# Sch_Sheet_Template.net
KiCad netlist of a schematic drawn in Altium Designer
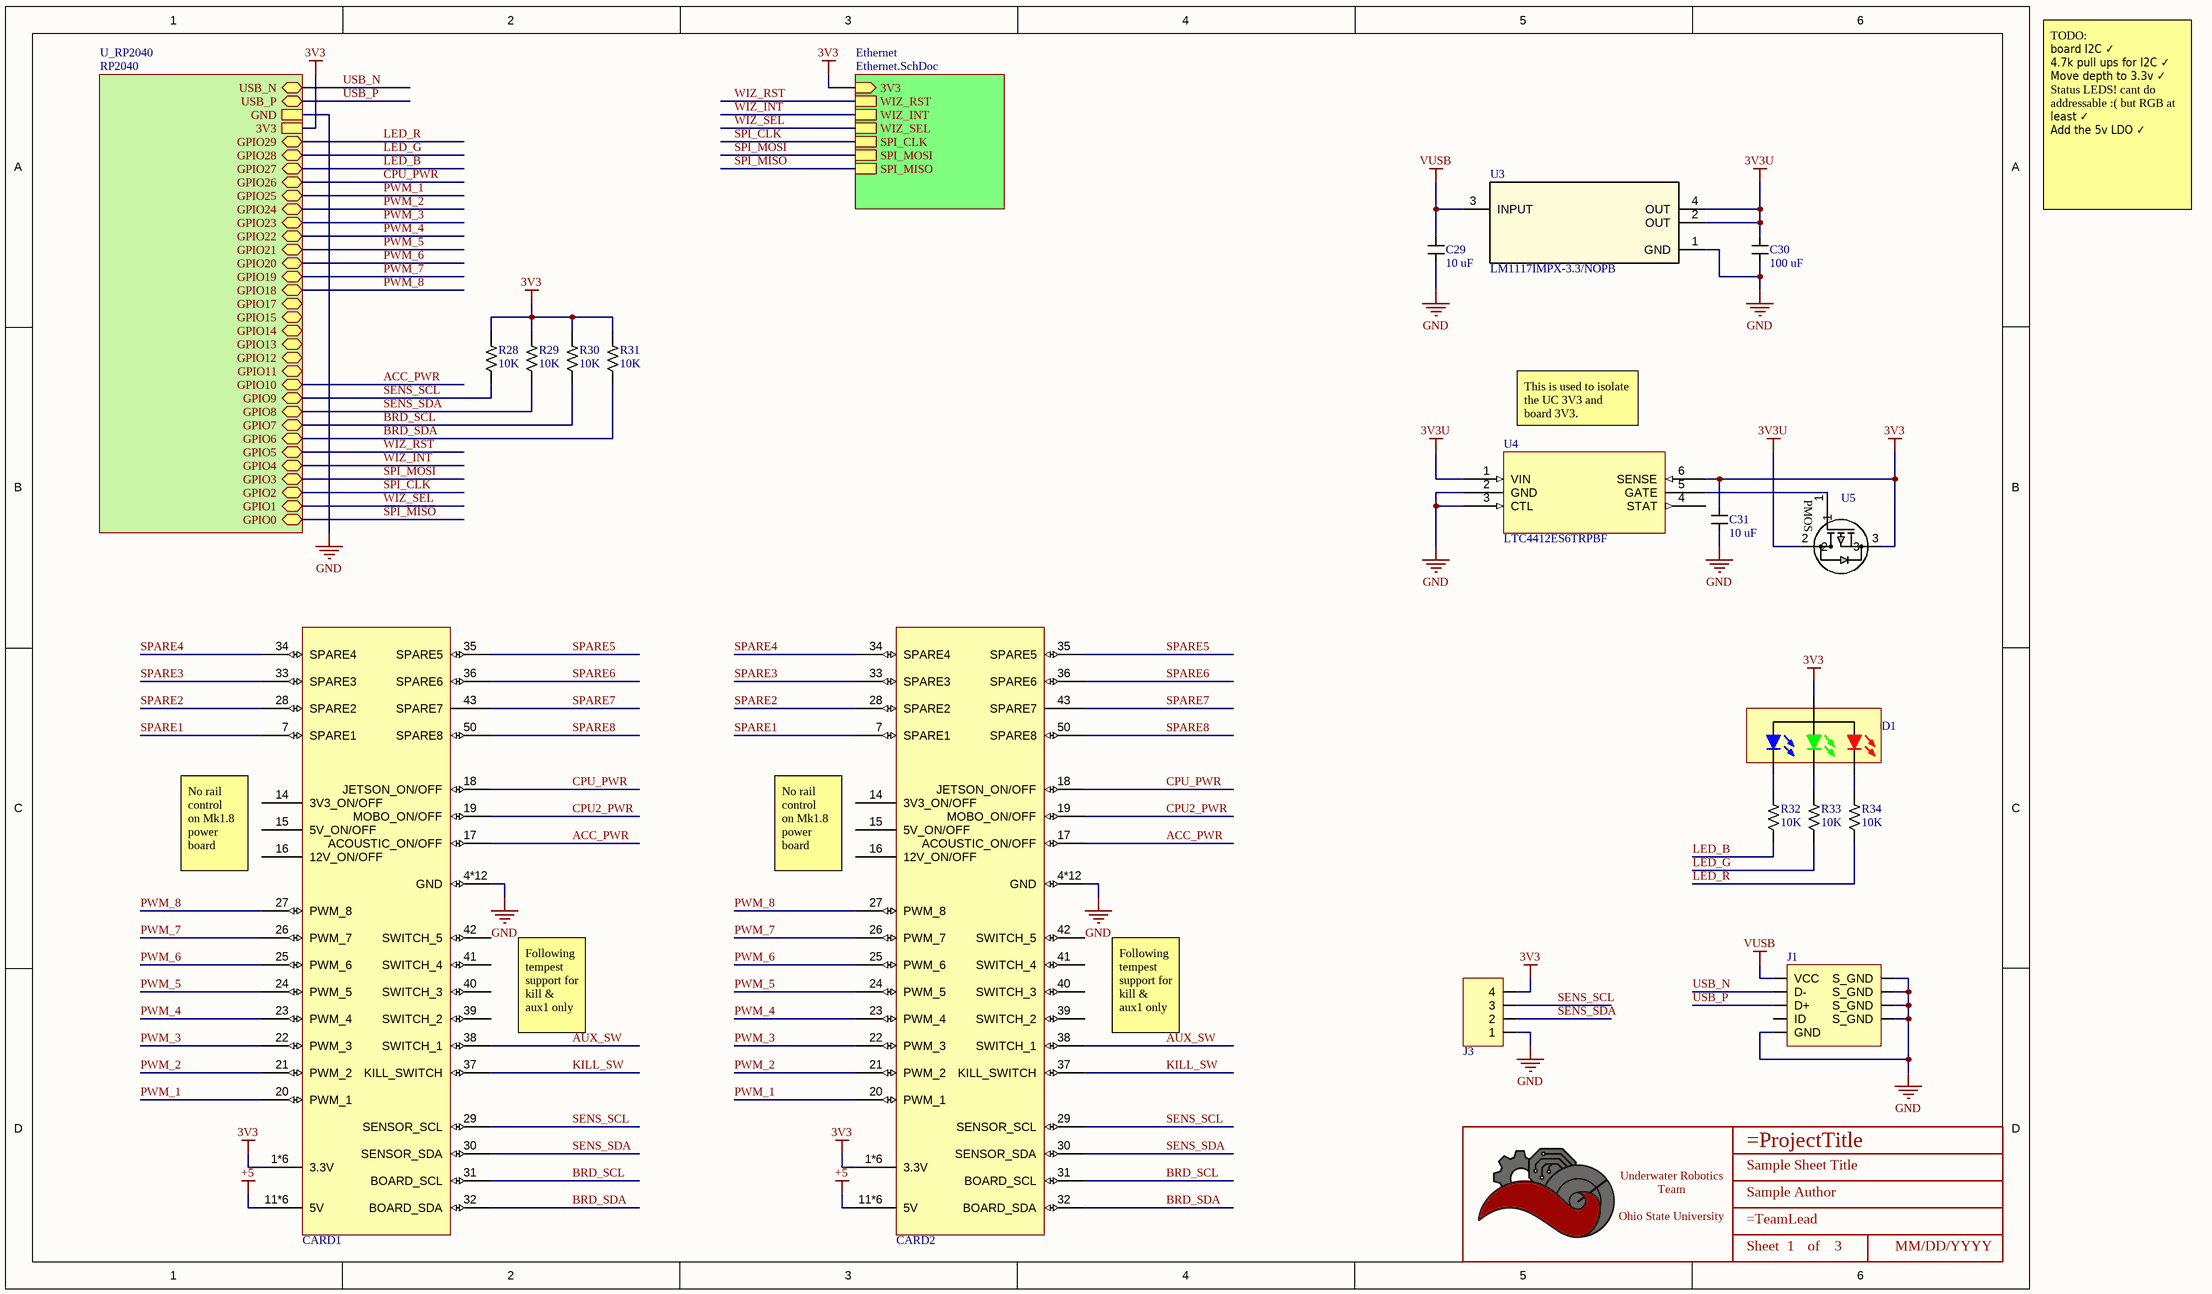
[diagram p0: Sch_Sheet_Template.SchDoc]

(export (version "E")
  (design (tool "Eeschema 10.0.6"))
  (components
    (comp (ref "*")
      (value "Title_Block")
      (footprint "LOGO")
      (description "UWRT Schematic Title Block Template\r\n\r\nCreated June 2021, Dylan Trainor")
      (libsource (lib "UWRT") (part "Title_Block"))
    )
    (comp (ref "C29")
      (value "10uF Ceramic 6.3V")
      (footprint "CAPACITOR_0603")
      (description "Cap 10uF 6.3V +/-20%\r\nCeramic 0603")
      (fields
        (field (name "TOLERANCE") "+/- 20%")
        (field (name "VOLTAGE") "6.3V")
        (field (name "VALUE (UF)") "10 uF")
        (field (name "MADE BY") "Flip B")
      )
      (libsource (lib "Capacitors") (part "CAPACITOR_10uF_0603"))
    )
    (comp (ref "C30")
      (value "100uF Ceramic 6.3V")
      (footprint "CAPACITOR_0603")
      (description "Cap 100uF 6.3V +/-20%\r\nCeramic 0603")
      (fields
        (field (name "TOLERANCE") "+/- 20%")
        (field (name "VOLTAGE") "6.3V")
        (field (name "VALUE (UF)") "100 uF")
        (field (name "MADE BY") "Dylan Trainor")
      )
      (libsource (lib "Capacitors") (part "CAPACITOR_100uF_0603"))
    )
    (comp (ref "C31")
      (value "10uF Ceramic 6.3V")
      (footprint "CAPACITOR_0603")
      (description "Cap 10uF 6.3V +/-20%\r\nCeramic 0603")
      (fields
        (field (name "TOLERANCE") "+/- 20%")
        (field (name "VOLTAGE") "6.3V")
        (field (name "VALUE (UF)") "10 uF")
        (field (name "MADE BY") "Flip B")
      )
      (libsource (lib "Capacitors") (part "CAPACITOR_10uF_0603"))
    )
    (comp (ref "CARD1")
      (value "BACKPLANE_EDGE_SOCKET")
      (footprint "SOCKET_BACKPLANE_EDGE_CONN")
      (description "Backplane Edge Socket")
      (fields (field (name "MADE BY") "Robert Pafford"))
      (libsource (lib "Connectors") (part "BACKPLANE_EDGE_SOCKET"))
    )
    (comp (ref "CARD2")
      (value "BACKPLANE_EDGE_SOCKET")
      (footprint "SOCKET_BACKPLANE_EDGE_CONN")
      (description "Backplane Edge Socket")
      (fields (field (name "MADE BY") "Robert Pafford"))
      (libsource (lib "Connectors") (part "BACKPLANE_EDGE_SOCKET"))
    )
    (comp (ref "D1")
      (value "EAST1616RGBB4")
      (footprint "LED_0606_4SMD")
      (description "LED RGB CLEAR 4SMD")
      (fields (field (name "MADE BY") "Robert Pafford"))
      (libsource (lib "Diodes") (part "LED_RGB_4SMD"))
    )
    (comp (ref "J1")
      (value "USB_MICRO R/A")
      (footprint "CONN_MINIUSB")
      (description "Amphenol Micro USB-B\r\nUSB2.0 5 Pin Right Angle SMD")
      (fields (field (name "MANUFACTURER") "Amphenol") (field (name "CREATED BY") "Flip B"))
      (libsource (lib "Connectors") (part "CONN_MICROUSB"))
    )
    (comp (ref "J3")
      (value "4 POS R/A")
      (footprint "CONN_MOLEX_MINIFIT JR_4 POS_R/A")
      (description "Molex Minifit Jr. 5569 \r\n4 Pos R/A Natural")
      (fields (field (name "MANUFACTURER") "Molex") (field (name "CREATED BY") "Flip B"))
      (libsource (lib "Connectors") (part "CONN_MOLEX_MINIFIT JR_4POS_R/A"))
    )
    (comp (ref "R28")
      (value "10k Ohm 5% 1/10W")
      (footprint "RESISTOR_0603")
      (description "RES 10k OHM 5% 1/10W 0603")
      (fields
        (field (name "TOLERANCE") "+/- 5%")
        (field (name "VALUE  (OHMS)") "10K")
        (field (name "MADE BY") "Robert Pafford")
      )
      (libsource (lib "Resistors") (part "RESISTOR_10K_0603"))
    )
    (comp (ref "R29")
      (value "10k Ohm 5% 1/10W")
      (footprint "RESISTOR_0603")
      (description "RES 10k OHM 5% 1/10W 0603")
      (fields
        (field (name "TOLERANCE") "+/- 5%")
        (field (name "VALUE  (OHMS)") "10K")
        (field (name "MADE BY") "Robert Pafford")
      )
      (libsource (lib "Resistors") (part "RESISTOR_10K_0603"))
    )
    (comp (ref "R30")
      (value "10k Ohm 5% 1/10W")
      (footprint "RESISTOR_0603")
      (description "RES 10k OHM 5% 1/10W 0603")
      (fields
        (field (name "TOLERANCE") "+/- 5%")
        (field (name "VALUE  (OHMS)") "10K")
        (field (name "MADE BY") "Robert Pafford")
      )
      (libsource (lib "Resistors") (part "RESISTOR_10K_0603"))
    )
    (comp (ref "R31")
      (value "10k Ohm 5% 1/10W")
      (footprint "RESISTOR_0603")
      (description "RES 10k OHM 5% 1/10W 0603")
      (fields
        (field (name "TOLERANCE") "+/- 5%")
        (field (name "VALUE  (OHMS)") "10K")
        (field (name "MADE BY") "Robert Pafford")
      )
      (libsource (lib "Resistors") (part "RESISTOR_10K_0603"))
    )
    (comp (ref "R32")
      (value "10k Ohm 5% 1/10W")
      (footprint "RESISTOR_0603")
      (description "RES 10k OHM 5% 1/10W 0603")
      (fields
        (field (name "TOLERANCE") "+/- 5%")
        (field (name "VALUE  (OHMS)") "10K")
        (field (name "MADE BY") "Robert Pafford")
      )
      (libsource (lib "Resistors") (part "RESISTOR_10K_0603"))
    )
    (comp (ref "R33")
      (value "10k Ohm 5% 1/10W")
      (footprint "RESISTOR_0603")
      (description "RES 10k OHM 5% 1/10W 0603")
      (fields
        (field (name "TOLERANCE") "+/- 5%")
        (field (name "VALUE  (OHMS)") "10K")
        (field (name "MADE BY") "Robert Pafford")
      )
      (libsource (lib "Resistors") (part "RESISTOR_10K_0603"))
    )
    (comp (ref "R34")
      (value "10k Ohm 5% 1/10W")
      (footprint "RESISTOR_0603")
      (description "RES 10k OHM 5% 1/10W 0603")
      (fields
        (field (name "TOLERANCE") "+/- 5%")
        (field (name "VALUE  (OHMS)") "10K")
        (field (name "MADE BY") "Robert Pafford")
      )
      (libsource (lib "Resistors") (part "RESISTOR_10K_0603"))
    )
    (comp (ref "U3")
      (value "LM1117IMPX-3.3/NOPB")
      (footprint "SOT-223-4")
      (description "IC REG LIN 3.3V 800MA SOT223-4")
      (fields
        (field (name "PARTNUMBER") "LM1117IMP-3.3/NOPB")
        (field (name "MANUFACTURER") "Texas Instruments")
        (field (name "CREATED BY") "Dylan T")
      )
      (libsource (lib "Converter") (part "LM1117IMPX-3.3/NOPB"))
    )
    (comp (ref "U4")
      (value "LTC4412ES6TRPBF")
      (footprint "Integrated Circuits:TSOT-23_S6")
      (description "OR Controller Source Selector Switch P-Channel 2:1 TSOT-23-6")
      (fields (field (name "MP") "LTC4412ES6#TRPBF") (field (name "MF") "Analog Devices"))
      (libsource (lib "Integrated Circuits") (part "LTC4412ES6TRPBF"))
    )
    (comp (ref "U5")
      (value "MOSFET P-CHANNEL 20V 4.7A SOT23")
      (footprint "SOT-23-3")
      (description "P-Channel 20 V 4.7A (Tc) 1.56W (Tc) Surface Mount SOT-23")
      (fields
        (field (name "MANUFACTURER_PART_NUMBER") "TSM500P02CX")
        (field (name "CREATED BY") "Robert Pafford")
      )
      (libsource (lib "Transistors") (part "TSM500P02CX"))
    )
  )
  (nets
    (net (code "1") (name "+5") (class "Default")
      (node (ref "CARD1") (pin "11*6") (pinfunction "5V_11*6") (pintype "power_in"))
      (node (ref "CARD2") (pin "11*6") (pinfunction "5V_11*6") (pintype "power_in"))
    )
    (net (code "2") (name "/ACC_PWR") (class "Default")
      (node (ref "CARD1") (pin "17") (pinfunction "ACOUSTIC_ON/OFF_17") (pintype "bidirectional"))
      (node (ref "CARD2") (pin "17") (pinfunction "ACOUSTIC_ON/OFF_17") (pintype "bidirectional"))
    )
    (net (code "3") (name "/AUX_SW") (class "Default")
      (node (ref "CARD1") (pin "38") (pinfunction "SWITCH_1_38") (pintype "bidirectional"))
      (node (ref "CARD2") (pin "38") (pinfunction "SWITCH_1_38") (pintype "bidirectional"))
    )
    (net (code "4") (name "/BRD_SCL") (class "Default")
      (node (ref "CARD1") (pin "31") (pinfunction "BOARD_SCL_31") (pintype "bidirectional"))
      (node (ref "CARD2") (pin "31") (pinfunction "BOARD_SCL_31") (pintype "bidirectional"))
      (node (ref "R30") (pin "2") (pinfunction "2_2") (pintype "passive"))
    )
    (net (code "5") (name "/BRD_SDA") (class "Default")
      (node (ref "CARD1") (pin "32") (pinfunction "BOARD_SDA_32") (pintype "bidirectional"))
      (node (ref "CARD2") (pin "32") (pinfunction "BOARD_SDA_32") (pintype "bidirectional"))
      (node (ref "R31") (pin "2") (pinfunction "2_2") (pintype "passive"))
    )
    (net (code "6") (name "/CPU2_PWR") (class "Default")
      (node (ref "CARD1") (pin "19") (pinfunction "MOBO_ON/OFF_19") (pintype "bidirectional"))
      (node (ref "CARD2") (pin "19") (pinfunction "MOBO_ON/OFF_19") (pintype "bidirectional"))
    )
    (net (code "7") (name "/CPU_PWR") (class "Default")
      (node (ref "CARD1") (pin "18") (pinfunction "JETSON_ON/OFF_18") (pintype "bidirectional"))
      (node (ref "CARD2") (pin "18") (pinfunction "JETSON_ON/OFF_18") (pintype "bidirectional"))
    )
    (net (code "14") (name "/KILL_SW") (class "Default")
      (node (ref "CARD1") (pin "37") (pinfunction "KILL_SWITCH_37") (pintype "bidirectional"))
      (node (ref "CARD2") (pin "37") (pinfunction "KILL_SWITCH_37") (pintype "bidirectional"))
    )
    (net (code "15") (name "/LED_B") (class "Default")
      (node (ref "R32") (pin "2") (pinfunction "2_2") (pintype "passive"))
    )
    (net (code "16") (name "/LED_G") (class "Default")
      (node (ref "R33") (pin "2") (pinfunction "2_2") (pintype "passive"))
    )
    (net (code "17") (name "/LED_R") (class "Default")
      (node (ref "R34") (pin "2") (pinfunction "2_2") (pintype "passive"))
    )
    (net (code "18") (name "/PWM_1") (class "Default")
      (node (ref "CARD1") (pin "20") (pinfunction "PWM_1_20") (pintype "bidirectional"))
      (node (ref "CARD2") (pin "20") (pinfunction "PWM_1_20") (pintype "bidirectional"))
    )
    (net (code "19") (name "/PWM_2") (class "Default")
      (node (ref "CARD1") (pin "21") (pinfunction "PWM_2_21") (pintype "bidirectional"))
      (node (ref "CARD2") (pin "21") (pinfunction "PWM_2_21") (pintype "bidirectional"))
    )
    (net (code "20") (name "/PWM_3") (class "Default")
      (node (ref "CARD1") (pin "22") (pinfunction "PWM_3_22") (pintype "bidirectional"))
      (node (ref "CARD2") (pin "22") (pinfunction "PWM_3_22") (pintype "bidirectional"))
    )
    (net (code "21") (name "/PWM_4") (class "Default")
      (node (ref "CARD1") (pin "23") (pinfunction "PWM_4_23") (pintype "bidirectional"))
      (node (ref "CARD2") (pin "23") (pinfunction "PWM_4_23") (pintype "bidirectional"))
    )
    (net (code "22") (name "/PWM_5") (class "Default")
      (node (ref "CARD1") (pin "24") (pinfunction "PWM_5_24") (pintype "bidirectional"))
      (node (ref "CARD2") (pin "24") (pinfunction "PWM_5_24") (pintype "bidirectional"))
    )
    (net (code "23") (name "/PWM_6") (class "Default")
      (node (ref "CARD1") (pin "25") (pinfunction "PWM_6_25") (pintype "bidirectional"))
      (node (ref "CARD2") (pin "25") (pinfunction "PWM_6_25") (pintype "bidirectional"))
    )
    (net (code "24") (name "/PWM_7") (class "Default")
      (node (ref "CARD1") (pin "26") (pinfunction "PWM_7_26") (pintype "bidirectional"))
      (node (ref "CARD2") (pin "26") (pinfunction "PWM_7_26") (pintype "bidirectional"))
    )
    (net (code "25") (name "/PWM_8") (class "Default")
      (node (ref "CARD1") (pin "27") (pinfunction "PWM_8_27") (pintype "bidirectional"))
      (node (ref "CARD2") (pin "27") (pinfunction "PWM_8_27") (pintype "bidirectional"))
    )
    (net (code "26") (name "/SENS_SCL") (class "Default")
      (node (ref "CARD1") (pin "29") (pinfunction "SENSOR_SCL_29") (pintype "bidirectional"))
      (node (ref "CARD2") (pin "29") (pinfunction "SENSOR_SCL_29") (pintype "bidirectional"))
      (node (ref "J3") (pin "3") (pinfunction "3_3") (pintype "passive"))
      (node (ref "R28") (pin "2") (pinfunction "2_2") (pintype "passive"))
    )
    (net (code "27") (name "/SENS_SDA") (class "Default")
      (node (ref "CARD1") (pin "30") (pinfunction "SENSOR_SDA_30") (pintype "bidirectional"))
      (node (ref "CARD2") (pin "30") (pinfunction "SENSOR_SDA_30") (pintype "bidirectional"))
      (node (ref "J3") (pin "2") (pinfunction "2_2") (pintype "passive"))
      (node (ref "R29") (pin "2") (pinfunction "2_2") (pintype "passive"))
    )
    (net (code "28") (name "/SPARE1") (class "Default")
      (node (ref "CARD1") (pin "7") (pinfunction "SPARE1_7") (pintype "bidirectional"))
      (node (ref "CARD2") (pin "7") (pinfunction "SPARE1_7") (pintype "bidirectional"))
    )
    (net (code "29") (name "/SPARE2") (class "Default")
      (node (ref "CARD1") (pin "28") (pinfunction "SPARE2_28") (pintype "bidirectional"))
      (node (ref "CARD2") (pin "28") (pinfunction "SPARE2_28") (pintype "bidirectional"))
    )
    (net (code "30") (name "/SPARE3") (class "Default")
      (node (ref "CARD1") (pin "33") (pinfunction "SPARE3_33") (pintype "bidirectional"))
      (node (ref "CARD2") (pin "33") (pinfunction "SPARE3_33") (pintype "bidirectional"))
    )
    (net (code "31") (name "/SPARE4") (class "Default")
      (node (ref "CARD1") (pin "34") (pinfunction "SPARE4_34") (pintype "bidirectional"))
      (node (ref "CARD2") (pin "34") (pinfunction "SPARE4_34") (pintype "bidirectional"))
    )
    (net (code "32") (name "/SPARE5") (class "Default")
      (node (ref "CARD1") (pin "35") (pinfunction "SPARE5_35") (pintype "bidirectional"))
      (node (ref "CARD2") (pin "35") (pinfunction "SPARE5_35") (pintype "bidirectional"))
    )
    (net (code "33") (name "/SPARE6") (class "Default")
      (node (ref "CARD1") (pin "36") (pinfunction "SPARE6_36") (pintype "bidirectional"))
      (node (ref "CARD2") (pin "36") (pinfunction "SPARE6_36") (pintype "bidirectional"))
    )
    (net (code "34") (name "/SPARE7") (class "Default")
      (node (ref "CARD1") (pin "43") (pinfunction "SPARE7_43") (pintype "power_in"))
      (node (ref "CARD2") (pin "43") (pinfunction "SPARE7_43") (pintype "power_in"))
    )
    (net (code "35") (name "/SPARE8") (class "Default")
      (node (ref "CARD1") (pin "50") (pinfunction "SPARE8_50") (pintype "bidirectional"))
      (node (ref "CARD2") (pin "50") (pinfunction "SPARE8_50") (pintype "bidirectional"))
    )
    (net (code "39") (name "/USB_N") (class "Default")
      (node (ref "J1") (pin "2") (pinfunction "D-_2") (pintype "passive"))
    )
    (net (code "40") (name "/USB_P") (class "Default")
      (node (ref "J1") (pin "3") (pinfunction "D+_3") (pintype "passive"))
    )
    (net (code "44") (name "3V3") (class "Default")
      (node (ref "C31") (pin "1") (pinfunction "1_1") (pintype "passive"))
      (node (ref "CARD1") (pin "1*6") (pinfunction "3.3V_1*6") (pintype "power_in"))
      (node (ref "CARD2") (pin "1*6") (pinfunction "3.3V_1*6") (pintype "power_in"))
      (node (ref "D1") (pin "4") (pinfunction "4_4") (pintype "passive"))
      (node (ref "J3") (pin "4") (pinfunction "4_4") (pintype "passive"))
      (node (ref "R28") (pin "1") (pinfunction "1_1") (pintype "passive"))
      (node (ref "R29") (pin "1") (pinfunction "1_1") (pintype "passive"))
      (node (ref "R30") (pin "1") (pinfunction "1_1") (pintype "passive"))
      (node (ref "R31") (pin "1") (pinfunction "1_1") (pintype "passive"))
      (node (ref "U4") (pin "6") (pinfunction "SENSE_6") (pintype "input"))
      (node (ref "U5") (pin "3") (pinfunction "3_3") (pintype "passive"))
    )
    (net (code "45") (name "3V3U") (class "Default")
      (node (ref "C30") (pin "1") (pinfunction "1_1") (pintype "passive"))
      (node (ref "U3") (pin "2") (pinfunction "OUT_2") (pintype "power_in"))
      (node (ref "U3") (pin "4") (pinfunction "OUT_4") (pintype "power_in"))
      (node (ref "U4") (pin "1") (pinfunction "VIN_1") (pintype "input"))
      (node (ref "U5") (pin "2") (pinfunction "2_2") (pintype "passive"))
    )
    (net (code "46") (name "GND") (class "Default")
      (node (ref "C29") (pin "2") (pinfunction "2_2") (pintype "passive"))
      (node (ref "C30") (pin "2") (pinfunction "2_2") (pintype "passive"))
      (node (ref "C31") (pin "2") (pinfunction "2_2") (pintype "passive"))
      (node (ref "CARD1") (pin "4*12") (pinfunction "GND_4*12") (pintype "bidirectional"))
      (node (ref "CARD2") (pin "4*12") (pinfunction "GND_4*12") (pintype "bidirectional"))
      (node (ref "J1") (pin "5") (pinfunction "GND_5") (pintype "passive"))
      (node (ref "J1") (pin "6") (pinfunction "S_GND_6") (pintype "passive"))
      (node (ref "J1") (pin "7") (pinfunction "S_GND_7") (pintype "passive"))
      (node (ref "J1") (pin "8") (pinfunction "S_GND_8") (pintype "passive"))
      (node (ref "J1") (pin "9") (pinfunction "S_GND_9") (pintype "passive"))
      (node (ref "J3") (pin "1") (pinfunction "1_1") (pintype "passive"))
      (node (ref "U3") (pin "1") (pinfunction "GND_1") (pintype "power_in"))
      (node (ref "U4") (pin "2") (pinfunction "GND_2") (pintype "power_in"))
      (node (ref "U4") (pin "3") (pinfunction "CTL_3") (pintype "input"))
    )
    (net (code "47") (name "Net-(D1-32)") (class "Default")
      (node (ref "D1") (pin "3") (pinfunction "32_3") (pintype "passive"))
      (node (ref "R32") (pin "1") (pinfunction "1_1") (pintype "passive"))
    )
    (net (code "48") (name "Net-(D1-Pad1)") (class "Default")
      (node (ref "D1") (pin "1") (pinfunction "1_1") (pintype "passive"))
      (node (ref "R34") (pin "1") (pinfunction "1_1") (pintype "passive"))
    )
    (net (code "49") (name "Net-(D1-Pad2)") (class "Default")
      (node (ref "D1") (pin "2") (pinfunction "2_2") (pintype "passive"))
      (node (ref "R33") (pin "1") (pinfunction "1_1") (pintype "passive"))
    )
    (net (code "50") (name "Net-(U4-GATE)") (class "Default")
      (node (ref "U4") (pin "5") (pinfunction "GATE_5") (pintype "passive"))
      (node (ref "U5") (pin "1") (pinfunction "1_1") (pintype "passive"))
    )
    (net (code "51") (name "VUSB") (class "Default")
      (node (ref "C29") (pin "1") (pinfunction "1_1") (pintype "passive"))
      (node (ref "J1") (pin "1") (pinfunction "VCC_1") (pintype "passive"))
      (node (ref "U3") (pin "3") (pinfunction "INPUT_3") (pintype "power_in"))
    )
    (net (code "52") (name "unconnected-(CARD1-3V3_ON{slash}OFF-Pad14)") (class "Default")
      (node (ref "CARD1") (pin "14") (pinfunction "3V3_ON/OFF_14") (pintype "power_in"))
    )
    (net (code "53") (name "unconnected-(CARD1-5V_ON{slash}OFF-Pad15)") (class "Default")
      (node (ref "CARD1") (pin "15") (pinfunction "5V_ON/OFF_15") (pintype "power_in"))
    )
    (net (code "54") (name "unconnected-(CARD1-12V_ON{slash}OFF-Pad16)") (class "Default")
      (node (ref "CARD1") (pin "16") (pinfunction "12V_ON/OFF_16") (pintype "power_in"))
    )
    (net (code "55") (name "unconnected-(CARD1-SWITCH_2-Pad39)") (class "Default")
      (node (ref "CARD1") (pin "39") (pinfunction "SWITCH_2_39") (pintype "bidirectional"))
    )
    (net (code "56") (name "unconnected-(CARD1-SWITCH_3-Pad40)") (class "Default")
      (node (ref "CARD1") (pin "40") (pinfunction "SWITCH_3_40") (pintype "bidirectional"))
    )
    (net (code "57") (name "unconnected-(CARD1-SWITCH_4-Pad41)") (class "Default")
      (node (ref "CARD1") (pin "41") (pinfunction "SWITCH_4_41") (pintype "bidirectional"))
    )
    (net (code "58") (name "unconnected-(CARD1-SWITCH_5-Pad42)") (class "Default")
      (node (ref "CARD1") (pin "42") (pinfunction "SWITCH_5_42") (pintype "bidirectional"))
    )
    (net (code "59") (name "unconnected-(CARD2-3V3_ON{slash}OFF-Pad14)") (class "Default")
      (node (ref "CARD2") (pin "14") (pinfunction "3V3_ON/OFF_14") (pintype "power_in"))
    )
    (net (code "60") (name "unconnected-(CARD2-5V_ON{slash}OFF-Pad15)") (class "Default")
      (node (ref "CARD2") (pin "15") (pinfunction "5V_ON/OFF_15") (pintype "power_in"))
    )
    (net (code "61") (name "unconnected-(CARD2-12V_ON{slash}OFF-Pad16)") (class "Default")
      (node (ref "CARD2") (pin "16") (pinfunction "12V_ON/OFF_16") (pintype "power_in"))
    )
    (net (code "62") (name "unconnected-(CARD2-SWITCH_2-Pad39)") (class "Default")
      (node (ref "CARD2") (pin "39") (pinfunction "SWITCH_2_39") (pintype "bidirectional"))
    )
    (net (code "63") (name "unconnected-(CARD2-SWITCH_3-Pad40)") (class "Default")
      (node (ref "CARD2") (pin "40") (pinfunction "SWITCH_3_40") (pintype "bidirectional"))
    )
    (net (code "64") (name "unconnected-(CARD2-SWITCH_4-Pad41)") (class "Default")
      (node (ref "CARD2") (pin "41") (pinfunction "SWITCH_4_41") (pintype "bidirectional"))
    )
    (net (code "65") (name "unconnected-(CARD2-SWITCH_5-Pad42)") (class "Default")
      (node (ref "CARD2") (pin "42") (pinfunction "SWITCH_5_42") (pintype "bidirectional"))
    )
    (net (code "66") (name "unconnected-(J1-ID-Pad4)") (class "Default")
      (node (ref "J1") (pin "4") (pinfunction "ID_4") (pintype "passive"))
    )
    (net (code "67") (name "unconnected-(U4-STAT-Pad4)") (class "Default")
      (node (ref "U4") (pin "4") (pinfunction "STAT_4") (pintype "output"))
    )
  )
)
